# RotaryEncoder_ArduinoAdapter.net
KiCad netlist of a schematic drawn in EAGLE
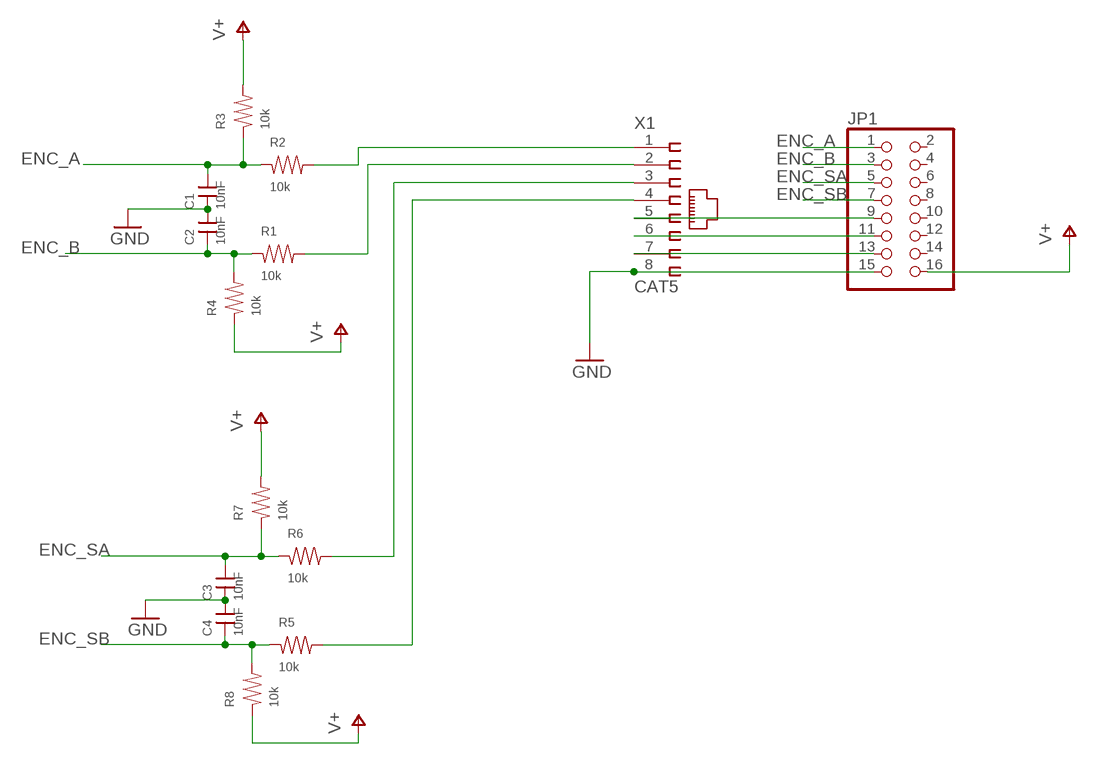
[diagram p0: schematic, sheet 1]

(export (version "E")
  (design (tool "Eeschema 10.0.6"))
  (components
    (comp (ref "C1")
      (value "10nF")
      (footprint "eagle-import:0603")
      (libsource (lib "eagle-import") (part "CAP0603"))
    )
    (comp (ref "C2")
      (value "10nF")
      (footprint "eagle-import:0603")
      (libsource (lib "eagle-import") (part "CAP0603"))
    )
    (comp (ref "C3")
      (value "10nF")
      (footprint "eagle-import:0603")
      (libsource (lib "eagle-import") (part "CAP0603"))
    )
    (comp (ref "C4")
      (value "10nF")
      (footprint "eagle-import:0603")
      (libsource (lib "eagle-import") (part "CAP0603"))
    )
    (comp (ref "JP1")
      (value "PINHD-2X8")
      (footprint "eagle-import:2X08")
      (libsource (lib "eagle-import") (part "PINHD-2X8"))
    )
    (comp (ref "R1")
      (value "10k")
      (footprint "eagle-import:0603")
      (libsource (lib "eagle-import") (part "RES0603"))
    )
    (comp (ref "R2")
      (value "10k")
      (footprint "eagle-import:0603")
      (libsource (lib "eagle-import") (part "RES0603"))
    )
    (comp (ref "R3")
      (value "10k")
      (footprint "eagle-import:0603")
      (libsource (lib "eagle-import") (part "RES0603"))
    )
    (comp (ref "R4")
      (value "10k")
      (footprint "eagle-import:0603")
      (libsource (lib "eagle-import") (part "RES0603"))
    )
    (comp (ref "R5")
      (value "10k")
      (footprint "eagle-import:0603")
      (libsource (lib "eagle-import") (part "RES0603"))
    )
    (comp (ref "R6")
      (value "10k")
      (footprint "eagle-import:0603")
      (libsource (lib "eagle-import") (part "RES0603"))
    )
    (comp (ref "R7")
      (value "10k")
      (footprint "eagle-import:0603")
      (libsource (lib "eagle-import") (part "RES0603"))
    )
    (comp (ref "R8")
      (value "10k")
      (footprint "eagle-import:0603")
      (libsource (lib "eagle-import") (part "RES0603"))
    )
    (comp (ref "X1")
      (value "CAT5")
      (footprint "eagle-import:555164-1")
      (libsource (lib "eagle-import") (part "CAT5"))
    )
  )
  (nets
    (net (code "1") (name "/ENC_A") (class "Default")
      (node (ref "C1") (pin "2") (pinfunction "P$2_2") (pintype "passive"))
      (node (ref "JP1") (pin "1") (pinfunction "1_1") (pintype "passive"))
      (node (ref "R2") (pin "1") (pinfunction "P$1_1") (pintype "passive"))
      (node (ref "R3") (pin "1") (pinfunction "P$1_1") (pintype "passive"))
    )
    (net (code "2") (name "/ENC_B") (class "Default")
      (node (ref "C2") (pin "1") (pinfunction "P$1_1") (pintype "passive"))
      (node (ref "JP1") (pin "3") (pinfunction "3_3") (pintype "passive"))
      (node (ref "R1") (pin "1") (pinfunction "P$1_1") (pintype "passive"))
      (node (ref "R4") (pin "2") (pinfunction "P$2_2") (pintype "passive"))
    )
    (net (code "3") (name "/ENC_SA") (class "Default")
      (node (ref "C3") (pin "2") (pinfunction "P$2_2") (pintype "passive"))
      (node (ref "JP1") (pin "5") (pinfunction "5_5") (pintype "passive"))
      (node (ref "R6") (pin "1") (pinfunction "P$1_1") (pintype "passive"))
      (node (ref "R7") (pin "1") (pinfunction "P$1_1") (pintype "passive"))
    )
    (net (code "4") (name "/ENC_SB") (class "Default")
      (node (ref "C4") (pin "1") (pinfunction "P$1_1") (pintype "passive"))
      (node (ref "JP1") (pin "7") (pinfunction "7_7") (pintype "passive"))
      (node (ref "R5") (pin "1") (pinfunction "P$1_1") (pintype "passive"))
      (node (ref "R8") (pin "2") (pinfunction "P$2_2") (pintype "passive"))
    )
    (net (code "5") (name "GND") (class "Default")
      (node (ref "C1") (pin "1") (pinfunction "P$1_1") (pintype "passive"))
      (node (ref "C2") (pin "2") (pinfunction "P$2_2") (pintype "passive"))
      (node (ref "C3") (pin "1") (pinfunction "P$1_1") (pintype "passive"))
      (node (ref "C4") (pin "2") (pinfunction "P$2_2") (pintype "passive"))
      (node (ref "JP1") (pin "15") (pinfunction "15_15") (pintype "passive"))
      (node (ref "X1") (pin "8") (pinfunction "8_8") (pintype "passive"))
    )
    (net (code "6") (name "Net-(JP1-Pad9)") (class "Default")
      (node (ref "JP1") (pin "9") (pinfunction "9_9") (pintype "passive"))
      (node (ref "X1") (pin "5") (pinfunction "5_5") (pintype "passive"))
    )
    (net (code "7") (name "Net-(JP1-Pad11)") (class "Default")
      (node (ref "JP1") (pin "11") (pinfunction "11_11") (pintype "passive"))
      (node (ref "X1") (pin "6") (pinfunction "6_6") (pintype "passive"))
    )
    (net (code "8") (name "Net-(JP1-Pad13)") (class "Default")
      (node (ref "JP1") (pin "13") (pinfunction "13_13") (pintype "passive"))
      (node (ref "X1") (pin "7") (pinfunction "7_7") (pintype "passive"))
    )
    (net (code "9") (name "Net-(R1-P$2)") (class "Default")
      (node (ref "R1") (pin "2") (pinfunction "P$2_2") (pintype "passive"))
      (node (ref "X1") (pin "2") (pinfunction "2_2") (pintype "passive"))
    )
    (net (code "10") (name "Net-(R2-P$2)") (class "Default")
      (node (ref "R2") (pin "2") (pinfunction "P$2_2") (pintype "passive"))
      (node (ref "X1") (pin "1") (pinfunction "1_1") (pintype "passive"))
    )
    (net (code "11") (name "Net-(R5-P$2)") (class "Default")
      (node (ref "R5") (pin "2") (pinfunction "P$2_2") (pintype "passive"))
      (node (ref "X1") (pin "4") (pinfunction "4_4") (pintype "passive"))
    )
    (net (code "12") (name "Net-(R6-P$2)") (class "Default")
      (node (ref "R6") (pin "2") (pinfunction "P$2_2") (pintype "passive"))
      (node (ref "X1") (pin "3") (pinfunction "3_3") (pintype "passive"))
    )
    (net (code "13") (name "V+") (class "Default")
      (node (ref "JP1") (pin "16") (pinfunction "16_16") (pintype "passive"))
      (node (ref "R3") (pin "2") (pinfunction "P$2_2") (pintype "passive"))
      (node (ref "R4") (pin "1") (pinfunction "P$1_1") (pintype "passive"))
      (node (ref "R7") (pin "2") (pinfunction "P$2_2") (pintype "passive"))
      (node (ref "R8") (pin "1") (pinfunction "P$1_1") (pintype "passive"))
    )
    (net (code "14") (name "unconnected-(JP1-Pad2)") (class "Default")
      (node (ref "JP1") (pin "2") (pinfunction "2_2") (pintype "passive"))
    )
    (net (code "15") (name "unconnected-(JP1-Pad4)") (class "Default")
      (node (ref "JP1") (pin "4") (pinfunction "4_4") (pintype "passive"))
    )
    (net (code "16") (name "unconnected-(JP1-Pad6)") (class "Default")
      (node (ref "JP1") (pin "6") (pinfunction "6_6") (pintype "passive"))
    )
    (net (code "17") (name "unconnected-(JP1-Pad8)") (class "Default")
      (node (ref "JP1") (pin "8") (pinfunction "8_8") (pintype "passive"))
    )
    (net (code "18") (name "unconnected-(JP1-Pad10)") (class "Default")
      (node (ref "JP1") (pin "10") (pinfunction "10_10") (pintype "passive"))
    )
    (net (code "19") (name "unconnected-(JP1-Pad12)") (class "Default")
      (node (ref "JP1") (pin "12") (pinfunction "12_12") (pintype "passive"))
    )
    (net (code "20") (name "unconnected-(JP1-Pad14)") (class "Default")
      (node (ref "JP1") (pin "14") (pinfunction "14_14") (pintype "passive"))
    )
  )
)
